# PSoC_PyunPyun_Mini.net
KiCad netlist of a schematic drawn in EAGLE
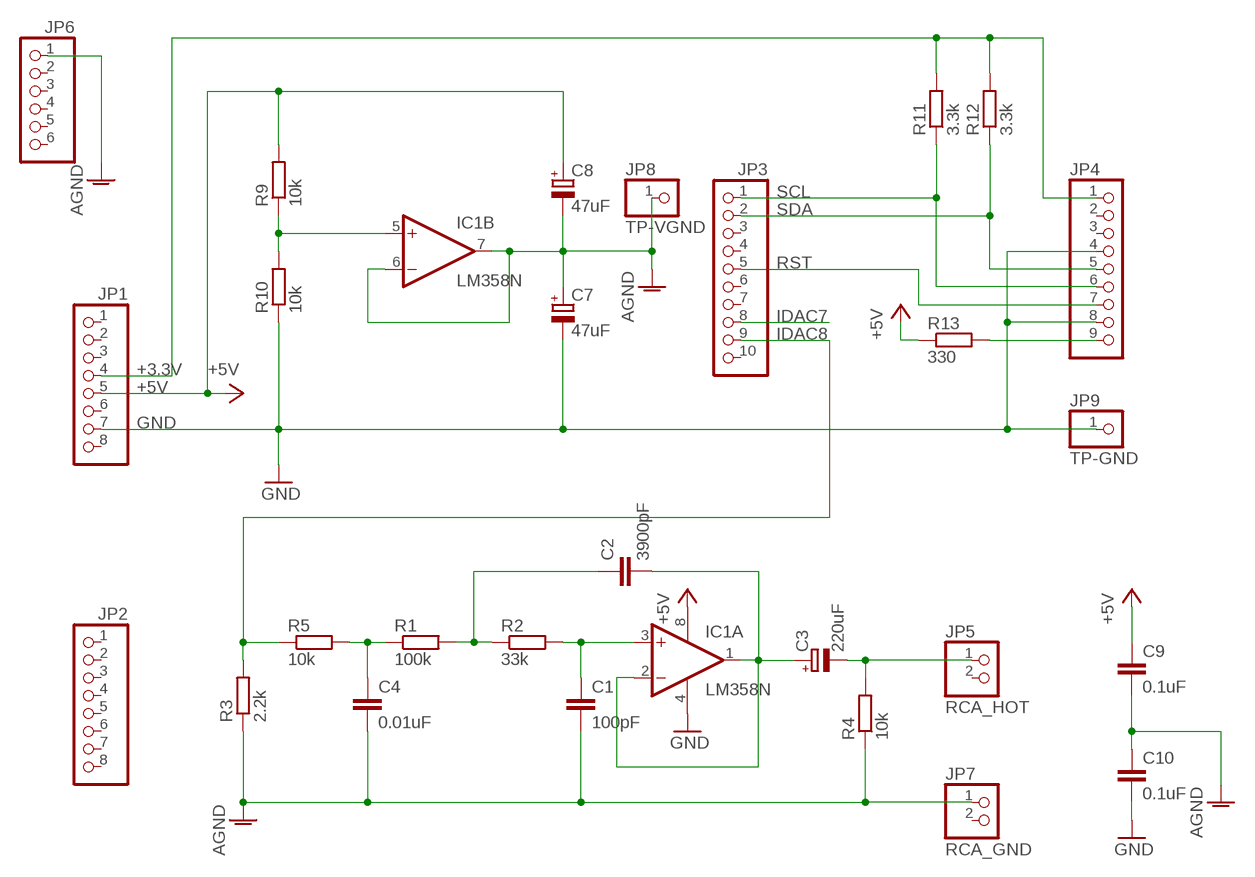
[diagram p0: schematic, sheet 1]

(export (version "E")
  (design (tool "Eeschema 10.0.6"))
  (components
    (comp (ref "C1")
      (value "100pF")
      (footprint "eagle-import:C050-024X044")
      (libsource (lib "eagle-import") (part "C-EU050-024X044"))
    )
    (comp (ref "C2")
      (value "3900pF")
      (footprint "eagle-import:C050-024X044")
      (libsource (lib "eagle-import") (part "C-EU050-024X044"))
    )
    (comp (ref "C3")
      (value "220uF")
      (footprint "eagle-import:E5-8,5")
      (libsource (lib "eagle-import") (part "CPOL-EUE5-8.5"))
    )
    (comp (ref "C4")
      (value "0.01uF")
      (footprint "eagle-import:C050-024X044")
      (libsource (lib "eagle-import") (part "C-EU050-024X044"))
    )
    (comp (ref "C7")
      (value "47uF")
      (footprint "eagle-import:E5-5")
      (libsource (lib "eagle-import") (part "CPOL-EUE5-5"))
    )
    (comp (ref "C8")
      (value "47uF")
      (footprint "eagle-import:E5-5")
      (libsource (lib "eagle-import") (part "CPOL-EUE5-5"))
    )
    (comp (ref "C9")
      (value "0.1uF")
      (footprint "eagle-import:C050-024X044")
      (libsource (lib "eagle-import") (part "C-EU050-024X044"))
    )
    (comp (ref "C10")
      (value "0.1uF")
      (footprint "eagle-import:C050-024X044")
      (libsource (lib "eagle-import") (part "C-EU050-024X044"))
    )
    (comp (ref "IC1")
      (value "LM358N")
      (footprint "eagle-import:DIL08")
      (libsource (lib "eagle-import") (part "LM358N"))
    )
    (comp (ref "JP1")
      (value "PINHD-1X8")
      (footprint "eagle-import:1X08")
      (libsource (lib "eagle-import") (part "PINHD-1X8"))
    )
    (comp (ref "JP2")
      (value "PINHD-1X8")
      (footprint "eagle-import:1X08")
      (libsource (lib "eagle-import") (part "PINHD-1X8"))
    )
    (comp (ref "JP3")
      (value "PINHD-1X10")
      (footprint "eagle-import:1X10")
      (libsource (lib "eagle-import") (part "PINHD-1X10"))
    )
    (comp (ref "JP4")
      (value "PINHD-1X9")
      (footprint "eagle-import:1X09")
      (libsource (lib "eagle-import") (part "PINHD-1X9"))
    )
    (comp (ref "JP5")
      (value "RCA_HOT")
      (footprint "eagle-import:1X02")
      (libsource (lib "eagle-import") (part "PINHD-1X2"))
    )
    (comp (ref "JP6")
      (value "PINHD-1X6")
      (footprint "eagle-import:1X06")
      (libsource (lib "eagle-import") (part "PINHD-1X6"))
    )
    (comp (ref "JP7")
      (value "RCA_GND")
      (footprint "eagle-import:1X02")
      (libsource (lib "eagle-import") (part "PINHD-1X2"))
    )
    (comp (ref "JP8")
      (value "TP-VGND")
      (footprint "eagle-import:1X01")
      (libsource (lib "eagle-import") (part "PINHD-1X1"))
    )
    (comp (ref "JP9")
      (value "TP-GND")
      (footprint "eagle-import:1X01")
      (libsource (lib "eagle-import") (part "PINHD-1X1"))
    )
    (comp (ref "R1")
      (value "100k")
      (footprint "eagle-import:0207_7")
      (libsource (lib "eagle-import") (part "R-EU_0207/7"))
    )
    (comp (ref "R2")
      (value "33k")
      (footprint "eagle-import:0207_7")
      (libsource (lib "eagle-import") (part "R-EU_0207/7"))
    )
    (comp (ref "R3")
      (value "2.2k")
      (footprint "eagle-import:0207_7")
      (libsource (lib "eagle-import") (part "R-EU_0207/7"))
    )
    (comp (ref "R4")
      (value "10k")
      (footprint "eagle-import:0207_7")
      (libsource (lib "eagle-import") (part "R-EU_0207/7"))
    )
    (comp (ref "R5")
      (value "10k")
      (footprint "eagle-import:0207_7")
      (libsource (lib "eagle-import") (part "R-EU_0207/7"))
    )
    (comp (ref "R9")
      (value "10k")
      (footprint "eagle-import:0207_7")
      (libsource (lib "eagle-import") (part "R-EU_0207/7"))
    )
    (comp (ref "R10")
      (value "10k")
      (footprint "eagle-import:0207_7")
      (libsource (lib "eagle-import") (part "R-EU_0207/7"))
    )
    (comp (ref "R11")
      (value "3.3k")
      (footprint "eagle-import:0207_7")
      (libsource (lib "eagle-import") (part "R-EU_0207/7"))
    )
    (comp (ref "R12")
      (value "3.3k")
      (footprint "eagle-import:0207_7")
      (libsource (lib "eagle-import") (part "R-EU_0207/7"))
    )
    (comp (ref "R13")
      (value "330")
      (footprint "eagle-import:0207_7")
      (libsource (lib "eagle-import") (part "R-EU_0207/7"))
    )
  )
  (nets
    (net (code "1") (name "+5V") (class "Default")
      (node (ref "C8") (pin "+") (pinfunction "+_+") (pintype "passive"))
      (node (ref "C9") (pin "1") (pinfunction "1_1") (pintype "passive"))
      (node (ref "IC1") (pin "8") (pinfunction "V+_8") (pintype "power_in"))
      (node (ref "JP1") (pin "5") (pinfunction "5_5") (pintype "passive"))
      (node (ref "R13") (pin "1") (pinfunction "1_1") (pintype "passive"))
      (node (ref "R9") (pin "2") (pinfunction "2_2") (pintype "passive"))
    )
    (net (code "2") (name "/+3.3V") (class "Default")
      (node (ref "JP1") (pin "4") (pinfunction "4_4") (pintype "passive"))
      (node (ref "JP4") (pin "1") (pinfunction "1_1") (pintype "passive"))
      (node (ref "R11") (pin "2") (pinfunction "2_2") (pintype "passive"))
      (node (ref "R12") (pin "2") (pinfunction "2_2") (pintype "passive"))
    )
    (net (code "3") (name "/IDAC7") (class "Default")
      (node (ref "JP3") (pin "8") (pinfunction "8_8") (pintype "passive"))
    )
    (net (code "4") (name "/IDAC8") (class "Default")
      (node (ref "JP3") (pin "9") (pinfunction "9_9") (pintype "passive"))
      (node (ref "R3") (pin "2") (pinfunction "2_2") (pintype "passive"))
      (node (ref "R5") (pin "1") (pinfunction "1_1") (pintype "passive"))
    )
    (net (code "5") (name "/RST") (class "Default")
      (node (ref "JP3") (pin "5") (pinfunction "5_5") (pintype "passive"))
      (node (ref "JP4") (pin "7") (pinfunction "7_7") (pintype "passive"))
    )
    (net (code "6") (name "/SCL") (class "Default")
      (node (ref "JP3") (pin "1") (pinfunction "1_1") (pintype "passive"))
      (node (ref "JP4") (pin "6") (pinfunction "6_6") (pintype "passive"))
      (node (ref "R11") (pin "1") (pinfunction "1_1") (pintype "passive"))
    )
    (net (code "7") (name "/SDA") (class "Default")
      (node (ref "JP3") (pin "2") (pinfunction "2_2") (pintype "passive"))
      (node (ref "JP4") (pin "5") (pinfunction "5_5") (pintype "passive"))
      (node (ref "R12") (pin "1") (pinfunction "1_1") (pintype "passive"))
    )
    (net (code "8") (name "AGND") (class "Default")
      (node (ref "C1") (pin "2") (pinfunction "2_2") (pintype "passive"))
      (node (ref "C10") (pin "1") (pinfunction "1_1") (pintype "passive"))
      (node (ref "C4") (pin "2") (pinfunction "2_2") (pintype "passive"))
      (node (ref "C7") (pin "+") (pinfunction "+_+") (pintype "passive"))
      (node (ref "C8") (pin "-") (pinfunction "-_-") (pintype "passive"))
      (node (ref "C9") (pin "2") (pinfunction "2_2") (pintype "passive"))
      (node (ref "IC1") (pin "6") (pinfunction "-IN_6") (pintype "input"))
      (node (ref "IC1") (pin "7") (pinfunction "OUT_7") (pintype "output"))
      (node (ref "JP6") (pin "1") (pinfunction "1_1") (pintype "passive"))
      (node (ref "JP7") (pin "1") (pinfunction "1_1") (pintype "passive"))
      (node (ref "JP8") (pin "1") (pinfunction "1_1") (pintype "passive"))
      (node (ref "R3") (pin "1") (pinfunction "1_1") (pintype "passive"))
      (node (ref "R4") (pin "1") (pinfunction "1_1") (pintype "passive"))
    )
    (net (code "9") (name "GND") (class "Default")
      (node (ref "C10") (pin "2") (pinfunction "2_2") (pintype "passive"))
      (node (ref "C7") (pin "-") (pinfunction "-_-") (pintype "passive"))
      (node (ref "IC1") (pin "4") (pinfunction "V-_4") (pintype "power_in"))
      (node (ref "JP1") (pin "7") (pinfunction "7_7") (pintype "passive"))
      (node (ref "JP4") (pin "4") (pinfunction "4_4") (pintype "passive"))
      (node (ref "JP4") (pin "8") (pinfunction "8_8") (pintype "passive"))
      (node (ref "JP9") (pin "1") (pinfunction "1_1") (pintype "passive"))
      (node (ref "R10") (pin "1") (pinfunction "1_1") (pintype "passive"))
    )
    (net (code "10") (name "Net-(C2-Pad1)") (class "Default")
      (node (ref "C2") (pin "1") (pinfunction "1_1") (pintype "passive"))
      (node (ref "R1") (pin "2") (pinfunction "2_2") (pintype "passive"))
      (node (ref "R2") (pin "1") (pinfunction "1_1") (pintype "passive"))
    )
    (net (code "11") (name "Net-(C3-Pad-)") (class "Default")
      (node (ref "C3") (pin "-") (pinfunction "-_-") (pintype "passive"))
      (node (ref "JP5") (pin "1") (pinfunction "1_1") (pintype "passive"))
      (node (ref "R4") (pin "2") (pinfunction "2_2") (pintype "passive"))
    )
    (net (code "12") (name "Net-(C4-Pad1)") (class "Default")
      (node (ref "C4") (pin "1") (pinfunction "1_1") (pintype "passive"))
      (node (ref "R1") (pin "1") (pinfunction "1_1") (pintype "passive"))
      (node (ref "R5") (pin "2") (pinfunction "2_2") (pintype "passive"))
    )
    (net (code "13") (name "Net-(IC1A-+IN)") (class "Default")
      (node (ref "C1") (pin "1") (pinfunction "1_1") (pintype "passive"))
      (node (ref "IC1") (pin "3") (pinfunction "+IN_3") (pintype "input"))
      (node (ref "R2") (pin "2") (pinfunction "2_2") (pintype "passive"))
    )
    (net (code "14") (name "Net-(IC1A--IN)") (class "Default")
      (node (ref "C2") (pin "2") (pinfunction "2_2") (pintype "passive"))
      (node (ref "C3") (pin "+") (pinfunction "+_+") (pintype "passive"))
      (node (ref "IC1") (pin "1") (pinfunction "OUT_1") (pintype "output"))
      (node (ref "IC1") (pin "2") (pinfunction "-IN_2") (pintype "input"))
    )
    (net (code "15") (name "Net-(IC1B-+IN)") (class "Default")
      (node (ref "IC1") (pin "5") (pinfunction "+IN_5") (pintype "input"))
      (node (ref "R10") (pin "2") (pinfunction "2_2") (pintype "passive"))
      (node (ref "R9") (pin "1") (pinfunction "1_1") (pintype "passive"))
    )
    (net (code "16") (name "Net-(JP4-Pad9)") (class "Default")
      (node (ref "JP4") (pin "9") (pinfunction "9_9") (pintype "passive"))
      (node (ref "R13") (pin "2") (pinfunction "2_2") (pintype "passive"))
    )
    (net (code "17") (name "unconnected-(JP1-Pad1)") (class "Default")
      (node (ref "JP1") (pin "1") (pinfunction "1_1") (pintype "passive"))
    )
    (net (code "18") (name "unconnected-(JP1-Pad2)") (class "Default")
      (node (ref "JP1") (pin "2") (pinfunction "2_2") (pintype "passive"))
    )
    (net (code "19") (name "unconnected-(JP1-Pad3)") (class "Default")
      (node (ref "JP1") (pin "3") (pinfunction "3_3") (pintype "passive"))
    )
    (net (code "20") (name "unconnected-(JP1-Pad6)") (class "Default")
      (node (ref "JP1") (pin "6") (pinfunction "6_6") (pintype "passive"))
    )
    (net (code "21") (name "unconnected-(JP1-Pad8)") (class "Default")
      (node (ref "JP1") (pin "8") (pinfunction "8_8") (pintype "passive"))
    )
    (net (code "22") (name "unconnected-(JP2-Pad1)") (class "Default")
      (node (ref "JP2") (pin "1") (pinfunction "1_1") (pintype "passive"))
    )
    (net (code "23") (name "unconnected-(JP2-Pad2)") (class "Default")
      (node (ref "JP2") (pin "2") (pinfunction "2_2") (pintype "passive"))
    )
    (net (code "24") (name "unconnected-(JP2-Pad3)") (class "Default")
      (node (ref "JP2") (pin "3") (pinfunction "3_3") (pintype "passive"))
    )
    (net (code "25") (name "unconnected-(JP2-Pad4)") (class "Default")
      (node (ref "JP2") (pin "4") (pinfunction "4_4") (pintype "passive"))
    )
    (net (code "26") (name "unconnected-(JP2-Pad5)") (class "Default")
      (node (ref "JP2") (pin "5") (pinfunction "5_5") (pintype "passive"))
    )
    (net (code "27") (name "unconnected-(JP2-Pad6)") (class "Default")
      (node (ref "JP2") (pin "6") (pinfunction "6_6") (pintype "passive"))
    )
    (net (code "28") (name "unconnected-(JP2-Pad7)") (class "Default")
      (node (ref "JP2") (pin "7") (pinfunction "7_7") (pintype "passive"))
    )
    (net (code "29") (name "unconnected-(JP2-Pad8)") (class "Default")
      (node (ref "JP2") (pin "8") (pinfunction "8_8") (pintype "passive"))
    )
    (net (code "30") (name "unconnected-(JP3-Pad3)") (class "Default")
      (node (ref "JP3") (pin "3") (pinfunction "3_3") (pintype "passive"))
    )
    (net (code "31") (name "unconnected-(JP3-Pad4)") (class "Default")
      (node (ref "JP3") (pin "4") (pinfunction "4_4") (pintype "passive"))
    )
    (net (code "32") (name "unconnected-(JP3-Pad6)") (class "Default")
      (node (ref "JP3") (pin "6") (pinfunction "6_6") (pintype "passive"))
    )
    (net (code "33") (name "unconnected-(JP3-Pad7)") (class "Default")
      (node (ref "JP3") (pin "7") (pinfunction "7_7") (pintype "passive"))
    )
    (net (code "34") (name "unconnected-(JP3-Pad10)") (class "Default")
      (node (ref "JP3") (pin "10") (pinfunction "10_10") (pintype "passive"))
    )
    (net (code "35") (name "unconnected-(JP4-Pad2)") (class "Default")
      (node (ref "JP4") (pin "2") (pinfunction "2_2") (pintype "passive"))
    )
    (net (code "36") (name "unconnected-(JP4-Pad3)") (class "Default")
      (node (ref "JP4") (pin "3") (pinfunction "3_3") (pintype "passive"))
    )
    (net (code "37") (name "unconnected-(JP5-Pad2)") (class "Default")
      (node (ref "JP5") (pin "2") (pinfunction "2_2") (pintype "passive"))
    )
    (net (code "38") (name "unconnected-(JP6-Pad2)") (class "Default")
      (node (ref "JP6") (pin "2") (pinfunction "2_2") (pintype "passive"))
    )
    (net (code "39") (name "unconnected-(JP6-Pad3)") (class "Default")
      (node (ref "JP6") (pin "3") (pinfunction "3_3") (pintype "passive"))
    )
    (net (code "40") (name "unconnected-(JP6-Pad4)") (class "Default")
      (node (ref "JP6") (pin "4") (pinfunction "4_4") (pintype "passive"))
    )
    (net (code "41") (name "unconnected-(JP6-Pad5)") (class "Default")
      (node (ref "JP6") (pin "5") (pinfunction "5_5") (pintype "passive"))
    )
    (net (code "42") (name "unconnected-(JP6-Pad6)") (class "Default")
      (node (ref "JP6") (pin "6") (pinfunction "6_6") (pintype "passive"))
    )
    (net (code "43") (name "unconnected-(JP7-Pad2)") (class "Default")
      (node (ref "JP7") (pin "2") (pinfunction "2_2") (pintype "passive"))
    )
  )
)
